# IOTBee.net
KiCad netlist of a schematic drawn in EAGLE
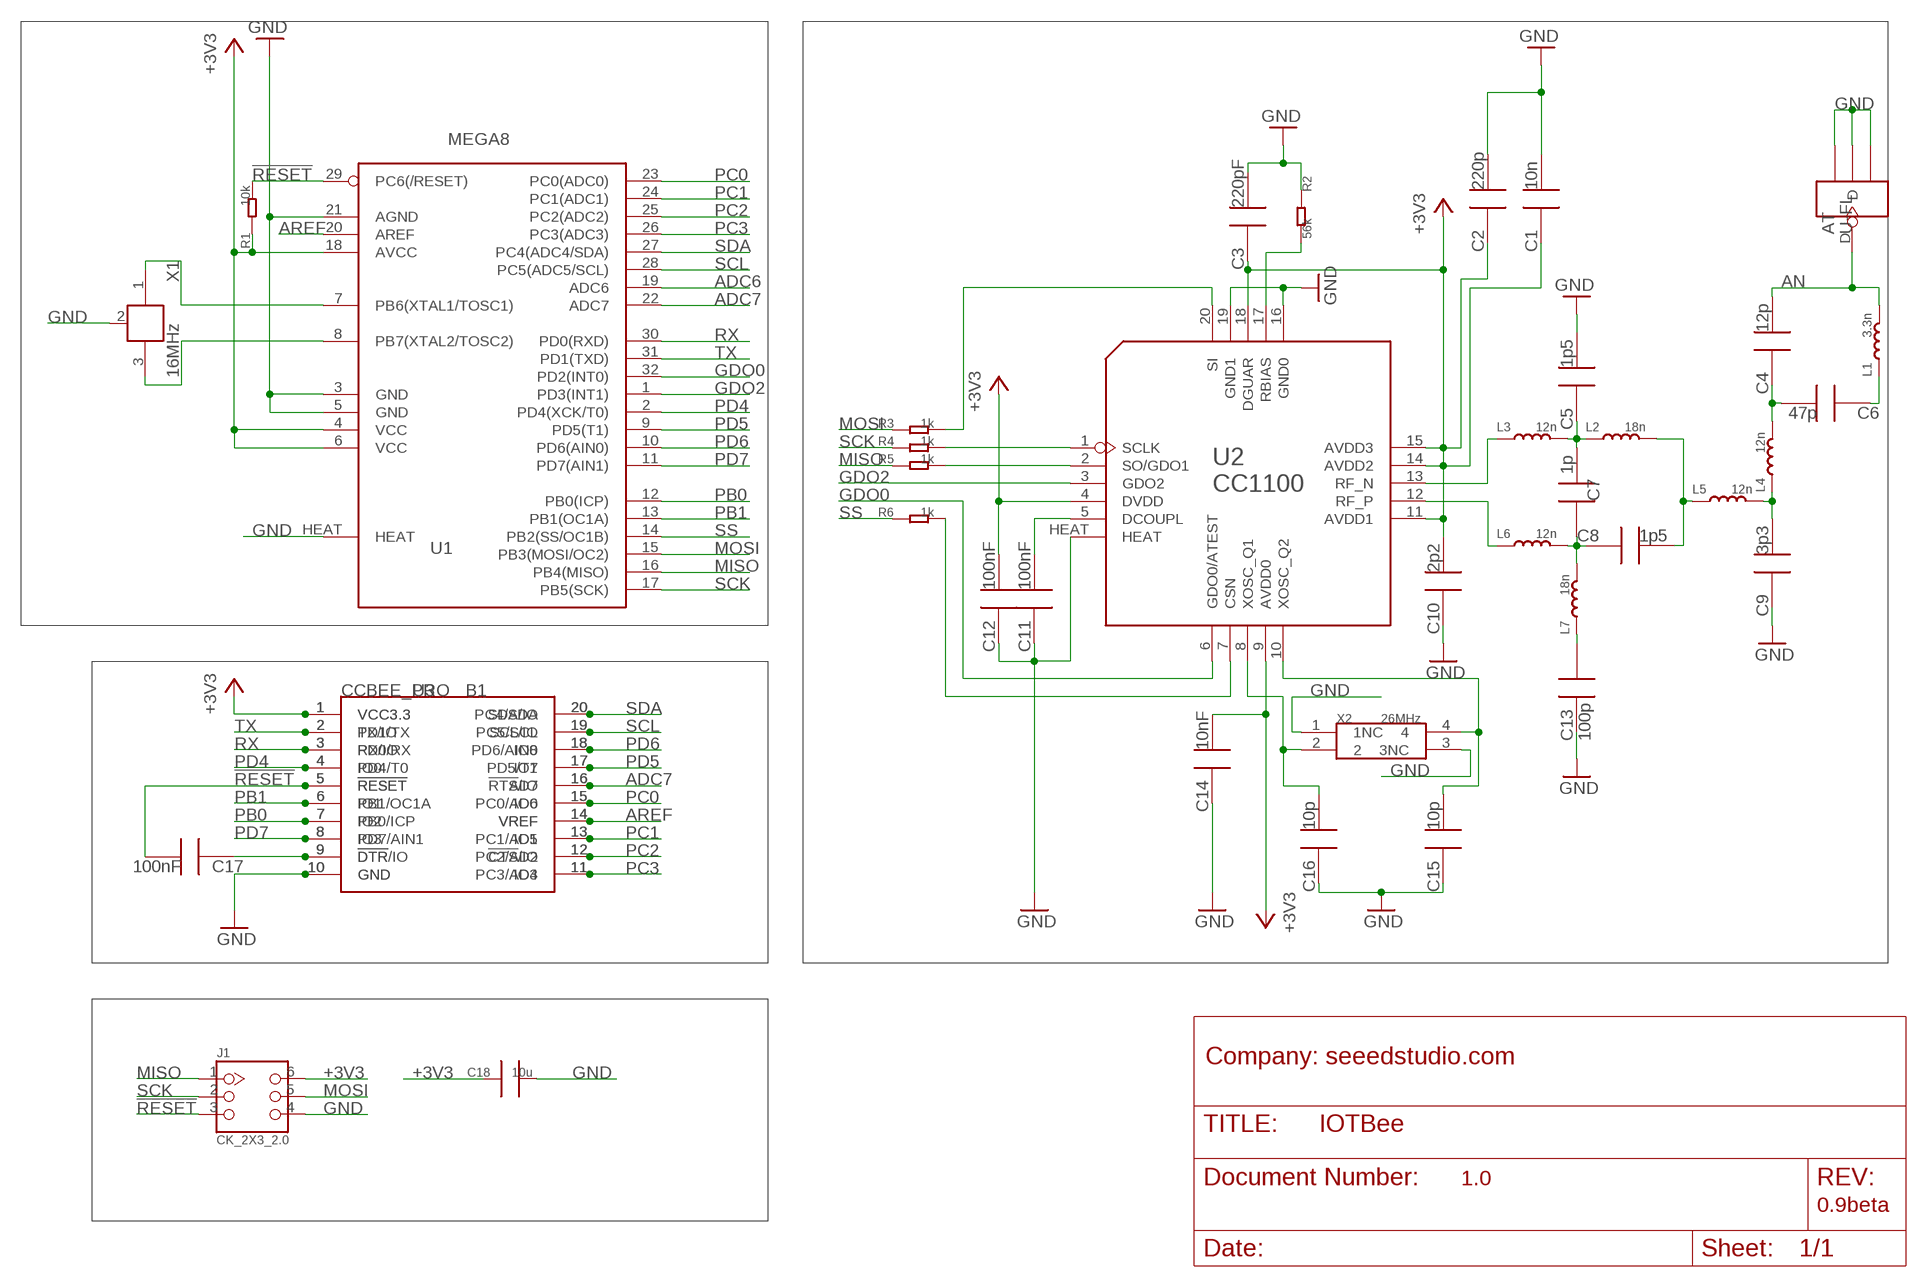
[diagram p0: schematic, sheet 1]

(export (version "E")
  (design (tool "Eeschema 10.0.6"))
  (components
    (comp (ref "AT")
      (value "U-FL")
      (footprint "eagle-import:U-FL")
      (libsource (lib "eagle-import") (part "U-FL"))
    )
    (comp (ref "B1")
      (value "CCBEE_PRO")
      (footprint "eagle-import:CCBEE-PRO")
      (libsource (lib "eagle-import") (part "CCBEE_PRO"))
    )
    (comp (ref "C1")
      (value "10n")
      (footprint "eagle-import:0603_S")
      (libsource (lib "eagle-import") (part "C0603_S"))
    )
    (comp (ref "C2")
      (value "220p")
      (footprint "eagle-import:0603_S")
      (libsource (lib "eagle-import") (part "C0603_S"))
    )
    (comp (ref "C3")
      (value "220pF")
      (footprint "eagle-import:0603_S")
      (libsource (lib "eagle-import") (part "C0603_S"))
    )
    (comp (ref "C4")
      (value "12p")
      (footprint "eagle-import:0603_S")
      (libsource (lib "eagle-import") (part "C0603_S"))
    )
    (comp (ref "C5")
      (value "1p5")
      (footprint "eagle-import:0603_S")
      (libsource (lib "eagle-import") (part "C0603_S"))
    )
    (comp (ref "C6")
      (value "47p")
      (footprint "eagle-import:0603_S")
      (libsource (lib "eagle-import") (part "C0603_S"))
    )
    (comp (ref "C7")
      (value "1p")
      (footprint "eagle-import:0603_S")
      (libsource (lib "eagle-import") (part "C0603_S"))
    )
    (comp (ref "C8")
      (value "1p5")
      (footprint "eagle-import:0603_S")
      (libsource (lib "eagle-import") (part "C0603_S"))
    )
    (comp (ref "C9")
      (value "3p3")
      (footprint "eagle-import:0603_S")
      (libsource (lib "eagle-import") (part "C0603_S"))
    )
    (comp (ref "C10")
      (value "2p2")
      (footprint "eagle-import:0603_S")
      (libsource (lib "eagle-import") (part "C0603_S"))
    )
    (comp (ref "C11")
      (value "100nF")
      (footprint "eagle-import:0603_S")
      (libsource (lib "eagle-import") (part "C0603_S"))
    )
    (comp (ref "C12")
      (value "100nF")
      (footprint "eagle-import:0603_S")
      (libsource (lib "eagle-import") (part "C0603_S"))
    )
    (comp (ref "C13")
      (value "100p")
      (footprint "eagle-import:0603_S")
      (libsource (lib "eagle-import") (part "C0603_S"))
    )
    (comp (ref "C14")
      (value "10nF")
      (footprint "eagle-import:0603_S")
      (libsource (lib "eagle-import") (part "C0603_S"))
    )
    (comp (ref "C15")
      (value "10p")
      (footprint "eagle-import:0603_S")
      (libsource (lib "eagle-import") (part "C0603_S"))
    )
    (comp (ref "C16")
      (value "10p")
      (footprint "eagle-import:0603_S")
      (libsource (lib "eagle-import") (part "C0603_S"))
    )
    (comp (ref "C17")
      (value "100nF")
      (footprint "eagle-import:0603_S")
      (libsource (lib "eagle-import") (part "C0603_S"))
    )
    (comp (ref "C18")
      (value "10u")
      (footprint "eagle-import:0805")
      (libsource (lib "eagle-import") (part "C0805"))
    )
    (comp (ref "J1")
      (value "CK_2X3_2.0")
      (footprint "eagle-import:CK_2X3_2.0")
      (libsource (lib "eagle-import") (part "CK_2X3_2.0"))
    )
    (comp (ref "L1")
      (value "3.3n")
      (footprint "eagle-import:0603_S")
      (libsource (lib "eagle-import") (part "L0603_S"))
    )
    (comp (ref "L2")
      (value "18n")
      (footprint "eagle-import:0603_S")
      (libsource (lib "eagle-import") (part "L0603_S"))
    )
    (comp (ref "L3")
      (value "12n")
      (footprint "eagle-import:0603_S")
      (libsource (lib "eagle-import") (part "L0603_S"))
    )
    (comp (ref "L4")
      (value "12n")
      (footprint "eagle-import:0603_S")
      (libsource (lib "eagle-import") (part "L0603_S"))
    )
    (comp (ref "L5")
      (value "12n")
      (footprint "eagle-import:0603_S")
      (libsource (lib "eagle-import") (part "L0603_S"))
    )
    (comp (ref "L6")
      (value "12n")
      (footprint "eagle-import:0603_S")
      (libsource (lib "eagle-import") (part "L0603_S"))
    )
    (comp (ref "L7")
      (value "18n")
      (footprint "eagle-import:0603_S")
      (libsource (lib "eagle-import") (part "L0603_S"))
    )
    (comp (ref "R1")
      (value "10k")
      (footprint "eagle-import:0603_S")
      (libsource (lib "eagle-import") (part "R0603_S"))
    )
    (comp (ref "R2")
      (value "56k")
      (footprint "eagle-import:0603_S")
      (libsource (lib "eagle-import") (part "R0603_S"))
    )
    (comp (ref "R3")
      (value "1k")
      (footprint "eagle-import:0603_S")
      (libsource (lib "eagle-import") (part "R0603_S"))
    )
    (comp (ref "R4")
      (value "1k")
      (footprint "eagle-import:0603_S")
      (libsource (lib "eagle-import") (part "R0603_S"))
    )
    (comp (ref "R5")
      (value "1k")
      (footprint "eagle-import:0603_S")
      (libsource (lib "eagle-import") (part "R0603_S"))
    )
    (comp (ref "R6")
      (value "1k")
      (footprint "eagle-import:0603_S")
      (libsource (lib "eagle-import") (part "R0603_S"))
    )
    (comp (ref "U1")
      (value "MEGA8")
      (footprint "eagle-import:MLF32X")
      (libsource (lib "eagle-import") (part "MEGA8"))
    )
    (comp (ref "U2")
      (value "CC1100")
      (footprint "eagle-import:QFN20")
      (libsource (lib "eagle-import") (part "CC1100"))
    )
    (comp (ref "U3")
      (value "BEE-OPENBEE-BTSMD")
      (footprint "eagle-import:20P-SMD-2.0-BT")
      (libsource (lib "eagle-import") (part "BEE-OPENBEE-BTSMD"))
    )
    (comp (ref "X1")
      (value "16MHz")
      (footprint "eagle-import:XTAL_3X2")
      (libsource (lib "eagle-import") (part "XTAL_NCVER"))
    )
    (comp (ref "X2")
      (value "26MHz")
      (footprint "eagle-import:X3225")
      (libsource (lib "eagle-import") (part "XTAL_SMD_3225"))
    )
  )
  (nets
    (net (code "1") (name "+3V3") (class "Default")
      (node (ref "B1") (pin "1") (pinfunction "VCC3.3_1") (pintype "bidirectional"))
      (node (ref "C1") (pin "1") (pinfunction "1_1") (pintype "bidirectional"))
      (node (ref "C10") (pin "2") (pinfunction "2_2") (pintype "bidirectional"))
      (node (ref "C12") (pin "2") (pinfunction "2_2") (pintype "bidirectional"))
      (node (ref "C14") (pin "2") (pinfunction "2_2") (pintype "bidirectional"))
      (node (ref "C18") (pin "1") (pinfunction "1_1") (pintype "bidirectional"))
      (node (ref "C2") (pin "1") (pinfunction "1_1") (pintype "bidirectional"))
      (node (ref "C3") (pin "1") (pinfunction "1_1") (pintype "bidirectional"))
      (node (ref "J1") (pin "6") (pinfunction "P$6_6") (pintype "bidirectional"))
      (node (ref "R1") (pin "1") (pinfunction "1_1") (pintype "bidirectional"))
      (node (ref "U1") (pin "18") (pinfunction "AVCC_18") (pintype "bidirectional"))
      (node (ref "U1") (pin "4") (pinfunction "VCC_4") (pintype "bidirectional"))
      (node (ref "U1") (pin "6") (pinfunction "VCC_6") (pintype "bidirectional"))
      (node (ref "U2") (pin "11") (pinfunction "AVDD1_11") (pintype "bidirectional"))
      (node (ref "U2") (pin "14") (pinfunction "AVDD2_14") (pintype "bidirectional"))
      (node (ref "U2") (pin "15") (pinfunction "AVDD3_15") (pintype "bidirectional"))
      (node (ref "U2") (pin "18") (pinfunction "DGUAR_18") (pintype "bidirectional"))
      (node (ref "U2") (pin "4") (pinfunction "DVDD_4") (pintype "bidirectional"))
      (node (ref "U2") (pin "9") (pinfunction "AVDD0_9") (pintype "bidirectional"))
      (node (ref "U3") (pin "1") (pinfunction "VCC3.3_1") (pintype "bidirectional"))
    )
    (net (code "2") (name "/ADC6") (class "Default")
      (node (ref "U1") (pin "19") (pinfunction "ADC6_19") (pintype "bidirectional"))
    )
    (net (code "3") (name "/ADC7") (class "Default")
      (node (ref "B1") (pin "16") (pinfunction "AD7_16") (pintype "bidirectional"))
      (node (ref "U1") (pin "22") (pinfunction "ADC7_22") (pintype "bidirectional"))
      (node (ref "U3") (pin "16") (pinfunction "~{RTS}/IO_16") (pintype "bidirectional"))
    )
    (net (code "4") (name "/AN") (class "Default")
      (node (ref "AT") (pin "D") (pinfunction "D_D") (pintype "bidirectional"))
      (node (ref "C4") (pin "2") (pinfunction "2_2") (pintype "bidirectional"))
      (node (ref "L1") (pin "2") (pinfunction "2_2") (pintype "bidirectional"))
    )
    (net (code "5") (name "/AREF") (class "Default")
      (node (ref "B1") (pin "14") (pinfunction "VREF_14") (pintype "bidirectional"))
      (node (ref "U1") (pin "20") (pinfunction "AREF_20") (pintype "bidirectional"))
      (node (ref "U3") (pin "14") (pinfunction "VREF_14") (pintype "bidirectional"))
    )
    (net (code "6") (name "/GDO0") (class "Default")
      (node (ref "U1") (pin "32") (pinfunction "PD2(INT0)_32") (pintype "bidirectional"))
      (node (ref "U2") (pin "6") (pinfunction "GDO0/ATEST_6") (pintype "bidirectional"))
    )
    (net (code "7") (name "/GDO2") (class "Default")
      (node (ref "U1") (pin "1") (pinfunction "PD3(INT1)_1") (pintype "bidirectional"))
      (node (ref "U2") (pin "3") (pinfunction "GDO2_3") (pintype "bidirectional"))
    )
    (net (code "8") (name "/MISO") (class "Default")
      (node (ref "J1") (pin "1") (pinfunction "P$1_1") (pintype "bidirectional"))
      (node (ref "R5") (pin "1") (pinfunction "1_1") (pintype "bidirectional"))
      (node (ref "U1") (pin "16") (pinfunction "PB4(MISO)_16") (pintype "bidirectional"))
    )
    (net (code "9") (name "/MOSI") (class "Default")
      (node (ref "J1") (pin "5") (pinfunction "P$5_5") (pintype "bidirectional"))
      (node (ref "R3") (pin "1") (pinfunction "1_1") (pintype "bidirectional"))
      (node (ref "U1") (pin "15") (pinfunction "PB3(MOSI/OC2)_15") (pintype "bidirectional"))
    )
    (net (code "10") (name "/PB0") (class "Default")
      (node (ref "B1") (pin "7") (pinfunction "PB0/ICP_7") (pintype "bidirectional"))
      (node (ref "U1") (pin "12") (pinfunction "PB0(ICP)_12") (pintype "bidirectional"))
      (node (ref "U3") (pin "7") (pinfunction "IO2_7") (pintype "bidirectional"))
    )
    (net (code "11") (name "/PB1") (class "Default")
      (node (ref "B1") (pin "6") (pinfunction "PB1/OC1A_6") (pintype "bidirectional"))
      (node (ref "U1") (pin "13") (pinfunction "PB1(OC1A)_13") (pintype "bidirectional"))
      (node (ref "U3") (pin "6") (pinfunction "IO1_6") (pintype "bidirectional"))
    )
    (net (code "12") (name "/PC0") (class "Default")
      (node (ref "B1") (pin "15") (pinfunction "PC0/AD0_15") (pintype "bidirectional"))
      (node (ref "U1") (pin "23") (pinfunction "PC0(ADC0)_23") (pintype "bidirectional"))
      (node (ref "U3") (pin "15") (pinfunction "IO6_15") (pintype "bidirectional"))
    )
    (net (code "13") (name "/PC1") (class "Default")
      (node (ref "B1") (pin "13") (pinfunction "PC1/AD1_13") (pintype "bidirectional"))
      (node (ref "U1") (pin "24") (pinfunction "PC1(ADC1)_24") (pintype "bidirectional"))
      (node (ref "U3") (pin "13") (pinfunction "IO5_13") (pintype "bidirectional"))
    )
    (net (code "14") (name "/PC2") (class "Default")
      (node (ref "B1") (pin "12") (pinfunction "PC2/AD2_12") (pintype "bidirectional"))
      (node (ref "U1") (pin "25") (pinfunction "PC2(ADC2)_25") (pintype "bidirectional"))
      (node (ref "U3") (pin "12") (pinfunction "~{CTS}/IO_12") (pintype "bidirectional"))
    )
    (net (code "15") (name "/PC3") (class "Default")
      (node (ref "B1") (pin "11") (pinfunction "PC3/AD3_11") (pintype "bidirectional"))
      (node (ref "U1") (pin "26") (pinfunction "PC3(ADC3)_26") (pintype "bidirectional"))
      (node (ref "U3") (pin "11") (pinfunction "IO4_11") (pintype "bidirectional"))
    )
    (net (code "16") (name "/PD4") (class "Default")
      (node (ref "B1") (pin "4") (pinfunction "PD4/T0_4") (pintype "bidirectional"))
      (node (ref "U1") (pin "2") (pinfunction "PD4(XCK/T0)_2") (pintype "bidirectional"))
      (node (ref "U3") (pin "4") (pinfunction "IO0_4") (pintype "bidirectional"))
    )
    (net (code "17") (name "/PD5") (class "Default")
      (node (ref "B1") (pin "17") (pinfunction "PD5/T1_17") (pintype "bidirectional"))
      (node (ref "U1") (pin "9") (pinfunction "PD5(T1)_9") (pintype "bidirectional"))
      (node (ref "U3") (pin "17") (pinfunction "IO7_17") (pintype "bidirectional"))
    )
    (net (code "18") (name "/PD6") (class "Default")
      (node (ref "B1") (pin "18") (pinfunction "PD6/AIN0_18") (pintype "bidirectional"))
      (node (ref "U1") (pin "10") (pinfunction "PD6(AIN0)_10") (pintype "bidirectional"))
      (node (ref "U3") (pin "18") (pinfunction "IO8_18") (pintype "bidirectional"))
    )
    (net (code "19") (name "/PD7") (class "Default")
      (node (ref "B1") (pin "8") (pinfunction "PD7/AIN1_8") (pintype "bidirectional"))
      (node (ref "U1") (pin "11") (pinfunction "PD7(AIN1)_11") (pintype "bidirectional"))
      (node (ref "U3") (pin "8") (pinfunction "IO3_8") (pintype "bidirectional"))
    )
    (net (code "20") (name "/RX") (class "Default")
      (node (ref "B1") (pin "3") (pinfunction "PD0/RX_3") (pintype "bidirectional"))
      (node (ref "U1") (pin "30") (pinfunction "PD0(RXD)_30") (pintype "bidirectional"))
      (node (ref "U3") (pin "3") (pinfunction "RX/IO_3") (pintype "bidirectional"))
    )
    (net (code "21") (name "/SCK") (class "Default")
      (node (ref "J1") (pin "2") (pinfunction "P$2_2") (pintype "bidirectional"))
      (node (ref "R4") (pin "1") (pinfunction "1_1") (pintype "bidirectional"))
      (node (ref "U1") (pin "17") (pinfunction "PB5(SCK)_17") (pintype "bidirectional"))
    )
    (net (code "22") (name "/SCL") (class "Default")
      (node (ref "B1") (pin "19") (pinfunction "PC5/SCL_19") (pintype "bidirectional"))
      (node (ref "U1") (pin "28") (pinfunction "PC5(ADC5/SCL)_28") (pintype "bidirectional"))
      (node (ref "U3") (pin "19") (pinfunction "SCL/IO_19") (pintype "bidirectional"))
    )
    (net (code "23") (name "/SDA") (class "Default")
      (node (ref "B1") (pin "20") (pinfunction "PC4/SDA_20") (pintype "bidirectional"))
      (node (ref "U1") (pin "27") (pinfunction "PC4(ADC4/SDA)_27") (pintype "bidirectional"))
      (node (ref "U3") (pin "20") (pinfunction "SDA/IO_20") (pintype "bidirectional"))
    )
    (net (code "24") (name "/SS") (class "Default")
      (node (ref "R6") (pin "1") (pinfunction "1_1") (pintype "bidirectional"))
      (node (ref "U1") (pin "14") (pinfunction "PB2(SS/OC1B)_14") (pintype "bidirectional"))
    )
    (net (code "25") (name "/TX") (class "Default")
      (node (ref "B1") (pin "2") (pinfunction "PD1/TX_2") (pintype "bidirectional"))
      (node (ref "U1") (pin "31") (pinfunction "PD1(TXD)_31") (pintype "bidirectional"))
      (node (ref "U3") (pin "2") (pinfunction "TX/IO_2") (pintype "bidirectional"))
    )
    (net (code "26") (name "/~{RESET}") (class "Default")
      (node (ref "B1") (pin "5") (pinfunction "~{RESET}_5") (pintype "bidirectional"))
      (node (ref "C17") (pin "2") (pinfunction "2_2") (pintype "bidirectional"))
      (node (ref "J1") (pin "3") (pinfunction "P$3_3") (pintype "bidirectional"))
      (node (ref "R1") (pin "2") (pinfunction "2_2") (pintype "bidirectional"))
      (node (ref "U1") (pin "29") (pinfunction "PC6(/RESET)_29") (pintype "bidirectional"))
      (node (ref "U3") (pin "5") (pinfunction "~{RESET}_5") (pintype "bidirectional"))
    )
    (net (code "27") (name "GND") (class "Default")
      (node (ref "AT") (pin "GND1") (pinfunction "GND1_GND1") (pintype "bidirectional"))
      (node (ref "AT") (pin "GND2") (pinfunction "GND2_GND2") (pintype "bidirectional"))
      (node (ref "AT") (pin "GND3") (pinfunction "GND3_GND3") (pintype "bidirectional"))
      (node (ref "B1") (pin "10") (pinfunction "GND_10") (pintype "bidirectional"))
      (node (ref "C1") (pin "2") (pinfunction "2_2") (pintype "bidirectional"))
      (node (ref "C10") (pin "1") (pinfunction "1_1") (pintype "bidirectional"))
      (node (ref "C11") (pin "1") (pinfunction "1_1") (pintype "bidirectional"))
      (node (ref "C12") (pin "1") (pinfunction "1_1") (pintype "bidirectional"))
      (node (ref "C13") (pin "1") (pinfunction "1_1") (pintype "bidirectional"))
      (node (ref "C14") (pin "1") (pinfunction "1_1") (pintype "bidirectional"))
      (node (ref "C15") (pin "1") (pinfunction "1_1") (pintype "bidirectional"))
      (node (ref "C16") (pin "1") (pinfunction "1_1") (pintype "bidirectional"))
      (node (ref "C18") (pin "2") (pinfunction "2_2") (pintype "bidirectional"))
      (node (ref "C2") (pin "2") (pinfunction "2_2") (pintype "bidirectional"))
      (node (ref "C3") (pin "2") (pinfunction "2_2") (pintype "bidirectional"))
      (node (ref "C5") (pin "2") (pinfunction "2_2") (pintype "bidirectional"))
      (node (ref "C9") (pin "1") (pinfunction "1_1") (pintype "bidirectional"))
      (node (ref "J1") (pin "4") (pinfunction "P$4_4") (pintype "bidirectional"))
      (node (ref "R2") (pin "1") (pinfunction "1_1") (pintype "bidirectional"))
      (node (ref "U1") (pin "21") (pinfunction "AGND_21") (pintype "bidirectional"))
      (node (ref "U1") (pin "3") (pinfunction "GND_3") (pintype "bidirectional"))
      (node (ref "U1") (pin "5") (pinfunction "GND_5") (pintype "bidirectional"))
      (node (ref "U1") (pin "HEAT") (pinfunction "HEAT_HEAT") (pintype "bidirectional"))
      (node (ref "U2") (pin "16") (pinfunction "GND0_16") (pintype "bidirectional"))
      (node (ref "U2") (pin "19") (pinfunction "GND1_19") (pintype "bidirectional"))
      (node (ref "U2") (pin "HEAT") (pinfunction "HEAT_HEAT") (pintype "bidirectional"))
      (node (ref "U3") (pin "10") (pinfunction "GND_10") (pintype "bidirectional"))
      (node (ref "X1") (pin "2") (pinfunction "GND_2") (pintype "bidirectional"))
      (node (ref "X2") (pin "1") (pinfunction "1NC_1") (pintype "bidirectional"))
      (node (ref "X2") (pin "3") (pinfunction "3NC_3") (pintype "bidirectional"))
    )
    (net (code "28") (name "Net-(B1-~{DTR})") (class "Default")
      (node (ref "B1") (pin "9") (pinfunction "~{DTR}_9") (pintype "bidirectional"))
      (node (ref "C17") (pin "1") (pinfunction "1_1") (pintype "bidirectional"))
      (node (ref "U3") (pin "9") (pinfunction "~{DTR}/IO_9") (pintype "bidirectional"))
    )
    (net (code "29") (name "Net-(C4-Pad1)") (class "Default")
      (node (ref "C4") (pin "1") (pinfunction "1_1") (pintype "bidirectional"))
      (node (ref "C6") (pin "2") (pinfunction "2_2") (pintype "bidirectional"))
      (node (ref "L4") (pin "2") (pinfunction "2_2") (pintype "bidirectional"))
    )
    (net (code "30") (name "Net-(C5-Pad1)") (class "Default")
      (node (ref "C5") (pin "1") (pinfunction "1_1") (pintype "bidirectional"))
      (node (ref "C7") (pin "2") (pinfunction "2_2") (pintype "bidirectional"))
      (node (ref "L2") (pin "1") (pinfunction "1_1") (pintype "bidirectional"))
      (node (ref "L3") (pin "2") (pinfunction "2_2") (pintype "bidirectional"))
    )
    (net (code "31") (name "Net-(C6-Pad1)") (class "Default")
      (node (ref "C6") (pin "1") (pinfunction "1_1") (pintype "bidirectional"))
      (node (ref "L1") (pin "1") (pinfunction "1_1") (pintype "bidirectional"))
    )
    (net (code "32") (name "Net-(C7-Pad1)") (class "Default")
      (node (ref "C7") (pin "1") (pinfunction "1_1") (pintype "bidirectional"))
      (node (ref "C8") (pin "1") (pinfunction "1_1") (pintype "bidirectional"))
      (node (ref "L6") (pin "2") (pinfunction "2_2") (pintype "bidirectional"))
      (node (ref "L7") (pin "2") (pinfunction "2_2") (pintype "bidirectional"))
    )
    (net (code "33") (name "Net-(C8-Pad2)") (class "Default")
      (node (ref "C8") (pin "2") (pinfunction "2_2") (pintype "bidirectional"))
      (node (ref "L2") (pin "2") (pinfunction "2_2") (pintype "bidirectional"))
      (node (ref "L5") (pin "1") (pinfunction "1_1") (pintype "bidirectional"))
    )
    (net (code "34") (name "Net-(C9-Pad2)") (class "Default")
      (node (ref "C9") (pin "2") (pinfunction "2_2") (pintype "bidirectional"))
      (node (ref "L4") (pin "1") (pinfunction "1_1") (pintype "bidirectional"))
      (node (ref "L5") (pin "2") (pinfunction "2_2") (pintype "bidirectional"))
    )
    (net (code "35") (name "Net-(C13-Pad2)") (class "Default")
      (node (ref "C13") (pin "2") (pinfunction "2_2") (pintype "bidirectional"))
      (node (ref "L7") (pin "1") (pinfunction "1_1") (pintype "bidirectional"))
    )
    (net (code "36") (name "Net-(U1-PB6(XTAL1{slash}TOSC1))") (class "Default")
      (node (ref "U1") (pin "7") (pinfunction "PB6(XTAL1/TOSC1)_7") (pintype "bidirectional"))
      (node (ref "X1") (pin "1") (pinfunction "1_1") (pintype "bidirectional"))
    )
    (net (code "37") (name "Net-(U1-PB7(XTAL2{slash}TOSC2))") (class "Default")
      (node (ref "U1") (pin "8") (pinfunction "PB7(XTAL2/TOSC2)_8") (pintype "bidirectional"))
      (node (ref "X1") (pin "3") (pinfunction "2_3") (pintype "bidirectional"))
    )
    (net (code "38") (name "Net-(U2-CSN)") (class "Default")
      (node (ref "R6") (pin "2") (pinfunction "2_2") (pintype "bidirectional"))
      (node (ref "U2") (pin "7") (pinfunction "CSN_7") (pintype "bidirectional"))
    )
    (net (code "39") (name "Net-(U2-DCOUPL)") (class "Default")
      (node (ref "C11") (pin "2") (pinfunction "2_2") (pintype "bidirectional"))
      (node (ref "U2") (pin "5") (pinfunction "DCOUPL_5") (pintype "bidirectional"))
    )
    (net (code "40") (name "Net-(U2-RBIAS)") (class "Default")
      (node (ref "R2") (pin "2") (pinfunction "2_2") (pintype "bidirectional"))
      (node (ref "U2") (pin "17") (pinfunction "RBIAS_17") (pintype "bidirectional"))
    )
    (net (code "41") (name "Net-(U2-RF_N)") (class "Default")
      (node (ref "L3") (pin "1") (pinfunction "1_1") (pintype "bidirectional"))
      (node (ref "U2") (pin "13") (pinfunction "RF_N_13") (pintype "bidirectional"))
    )
    (net (code "42") (name "Net-(U2-RF_P)") (class "Default")
      (node (ref "L6") (pin "1") (pinfunction "1_1") (pintype "bidirectional"))
      (node (ref "U2") (pin "12") (pinfunction "RF_P_12") (pintype "bidirectional"))
    )
    (net (code "43") (name "Net-(U2-SCLK)") (class "Default")
      (node (ref "R4") (pin "2") (pinfunction "2_2") (pintype "bidirectional"))
      (node (ref "U2") (pin "1") (pinfunction "SCLK_1") (pintype "bidirectional"))
    )
    (net (code "44") (name "Net-(U2-SI)") (class "Default")
      (node (ref "R3") (pin "2") (pinfunction "2_2") (pintype "bidirectional"))
      (node (ref "U2") (pin "20") (pinfunction "SI_20") (pintype "bidirectional"))
    )
    (net (code "45") (name "Net-(U2-SO{slash}GDO1)") (class "Default")
      (node (ref "R5") (pin "2") (pinfunction "2_2") (pintype "bidirectional"))
      (node (ref "U2") (pin "2") (pinfunction "SO/GDO1_2") (pintype "bidirectional"))
    )
    (net (code "46") (name "Net-(U2-XOSC_Q1)") (class "Default")
      (node (ref "C16") (pin "2") (pinfunction "2_2") (pintype "bidirectional"))
      (node (ref "U2") (pin "8") (pinfunction "XOSC_Q1_8") (pintype "bidirectional"))
      (node (ref "X2") (pin "2") (pinfunction "2_2") (pintype "bidirectional"))
    )
    (net (code "47") (name "Net-(U2-XOSC_Q2)") (class "Default")
      (node (ref "C15") (pin "2") (pinfunction "2_2") (pintype "bidirectional"))
      (node (ref "U2") (pin "10") (pinfunction "XOSC_Q2_10") (pintype "bidirectional"))
      (node (ref "X2") (pin "4") (pinfunction "4_4") (pintype "bidirectional"))
    )
  )
)
